# User_Control-Sliders.net
KiCad netlist of a schematic drawn in Altium Designer
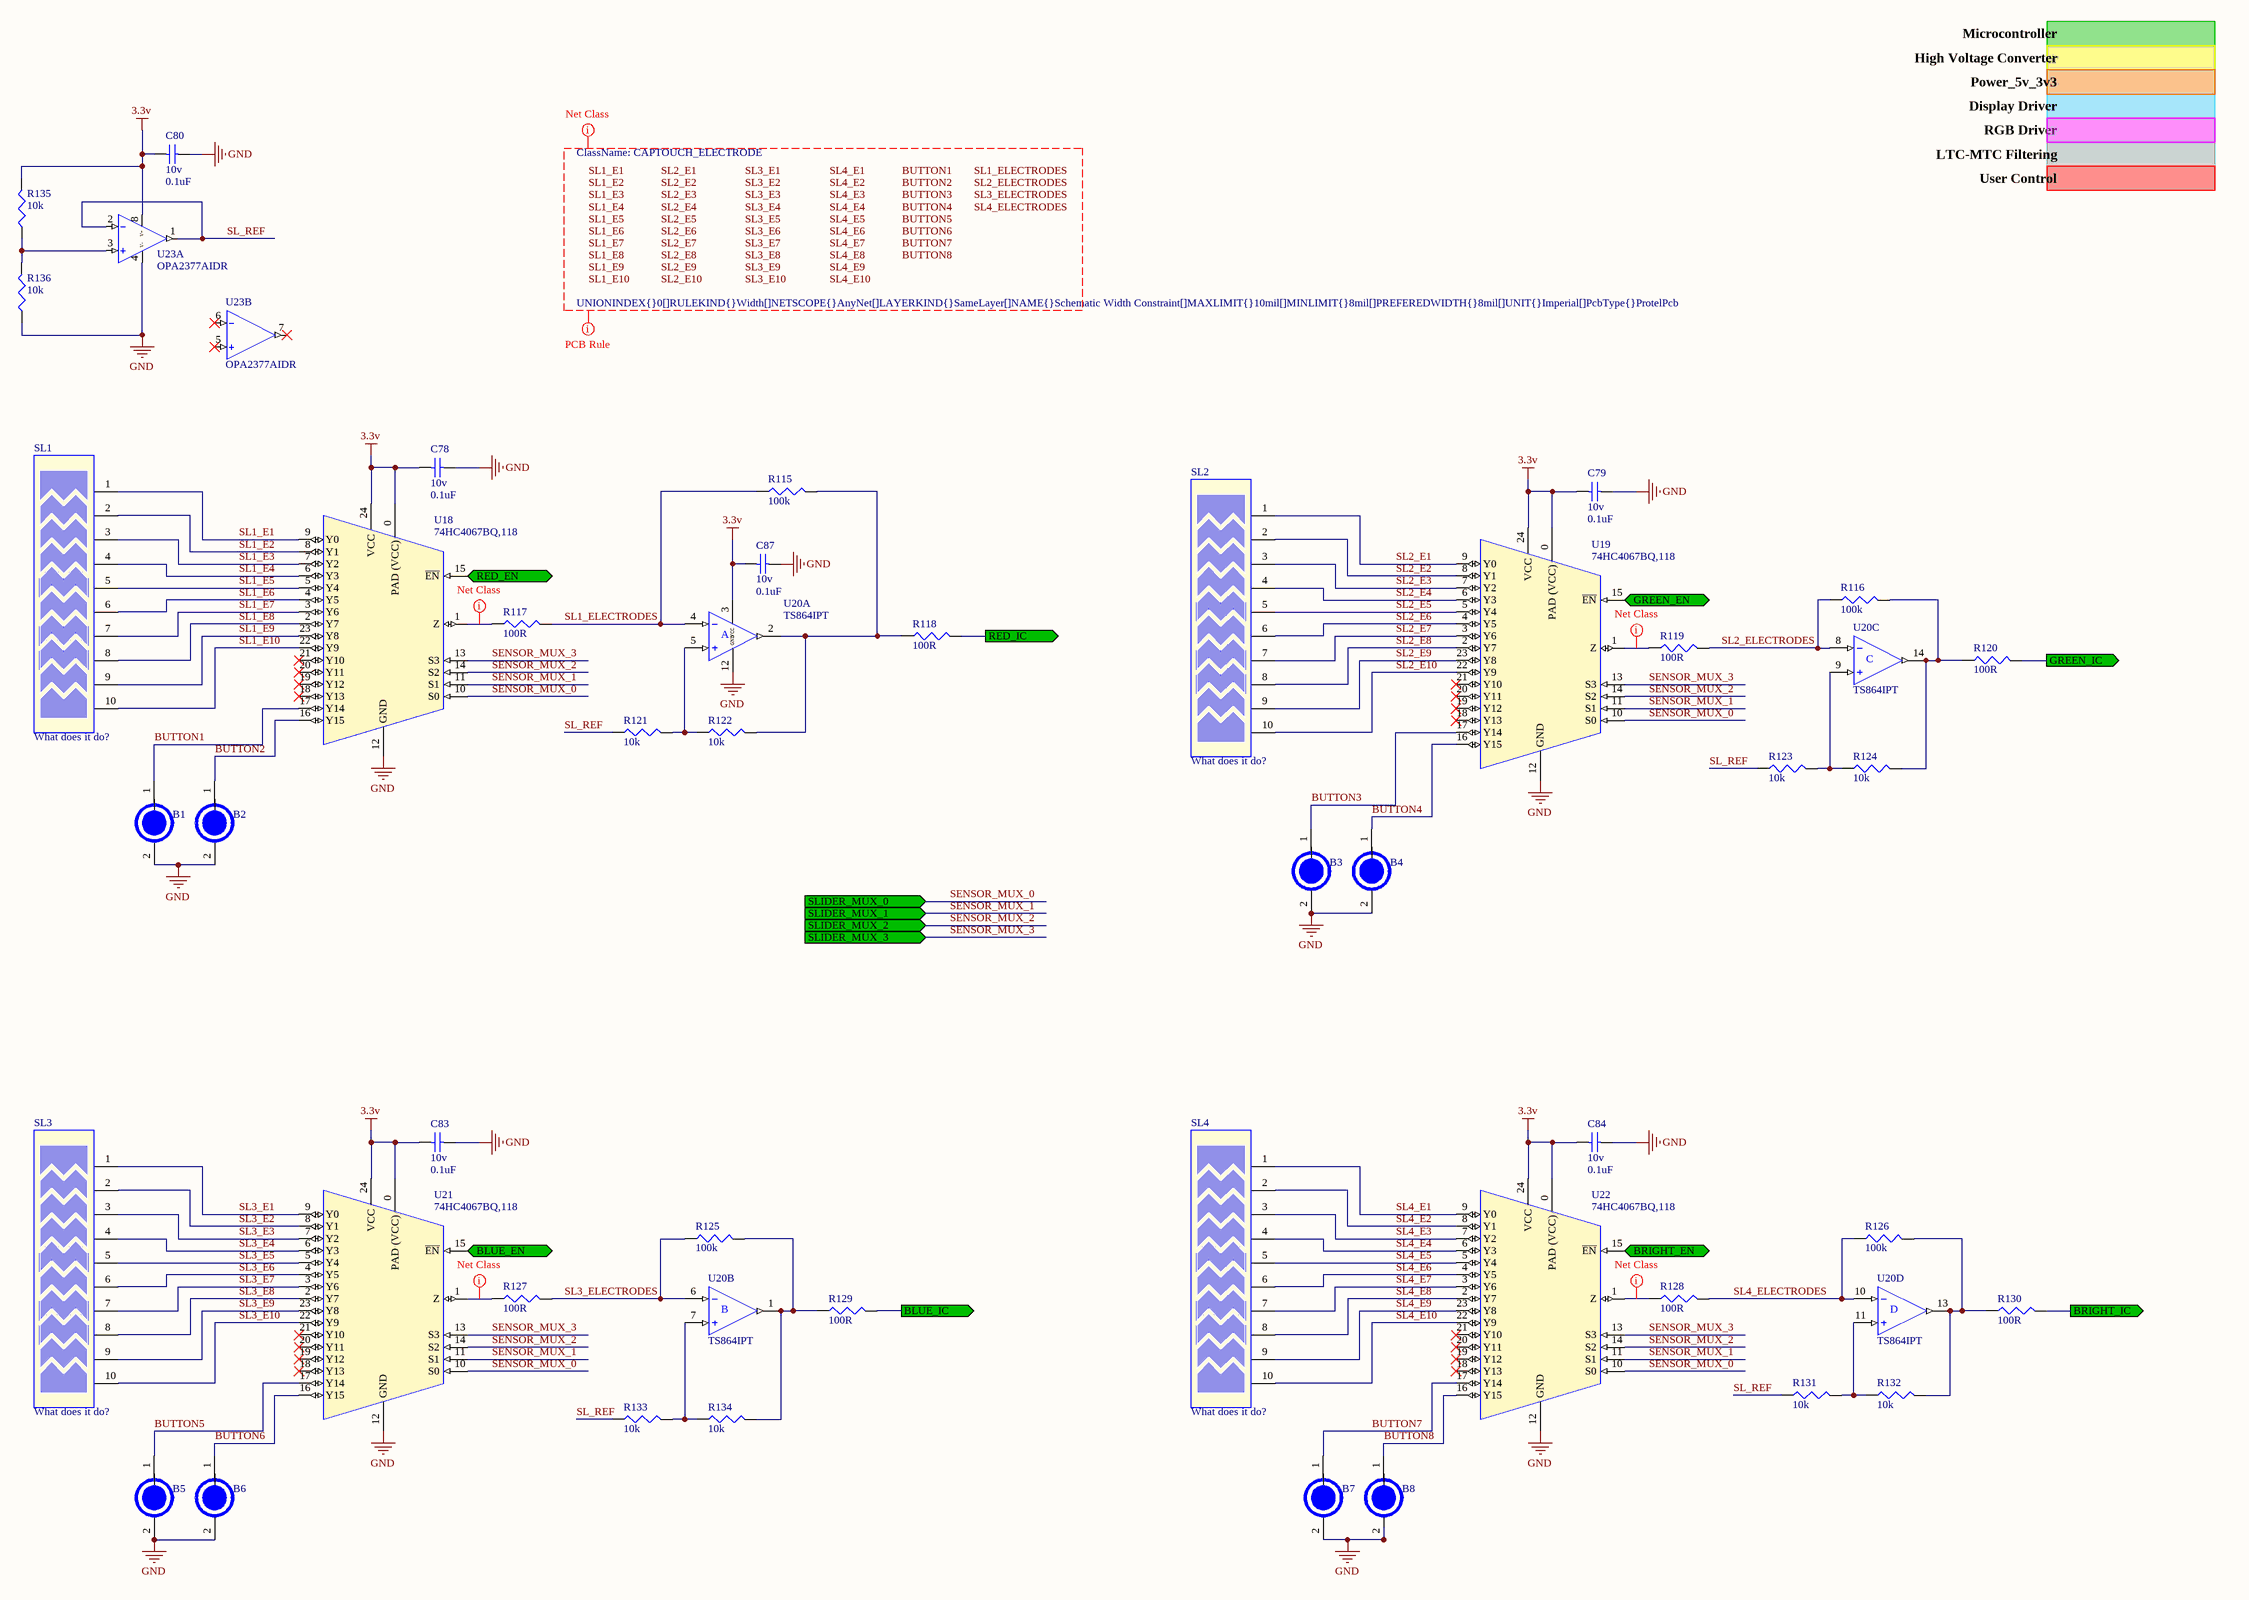
[diagram p0: User Control-Sliders.SchDoc]

(export (version "E")
  (design (tool "Eeschema 10.0.6"))
  (components
    (comp (ref "B1")
      (value "Cap Touch Button")
      (footprint "Cap Touch Button 10mm")
      (libsource (lib "Altium Library") (part "Cap Touch Button 10mm"))
    )
    (comp (ref "B2")
      (value "Cap Touch Button")
      (footprint "Cap Touch Button 10mm")
      (libsource (lib "Altium Library") (part "Cap Touch Button 10mm"))
    )
    (comp (ref "B3")
      (value "Cap Touch Button")
      (footprint "Cap Touch Button 10mm")
      (libsource (lib "Altium Library") (part "Cap Touch Button 10mm"))
    )
    (comp (ref "B4")
      (value "Cap Touch Button")
      (footprint "Cap Touch Button 10mm")
      (libsource (lib "Altium Library") (part "Cap Touch Button 10mm"))
    )
    (comp (ref "B5")
      (value "Cap Touch Button")
      (footprint "Cap Touch Button 10mm")
      (libsource (lib "Altium Library") (part "Cap Touch Button 10mm"))
    )
    (comp (ref "B6")
      (value "Cap Touch Button")
      (footprint "Cap Touch Button 10mm")
      (libsource (lib "Altium Library") (part "Cap Touch Button 10mm"))
    )
    (comp (ref "B7")
      (value "Cap Touch Button")
      (footprint "Cap Touch Button 10mm")
      (libsource (lib "Altium Library") (part "Cap Touch Button 10mm"))
    )
    (comp (ref "B8")
      (value "Cap Touch Button")
      (footprint "Cap Touch Button 10mm")
      (libsource (lib "Altium Library") (part "Cap Touch Button 10mm"))
    )
    (comp (ref "C78")
      (value "0.1uF")
      (footprint "CAP0402R")
      (fields (field (name "TOLERANCE") "20%") (field (name "MFG") "Vishay") (field (name "VOLTAGE") "10v"))
      (libsource (lib "Altium Library") (part "0.1uF 10v (0402)"))
    )
    (comp (ref "C79")
      (value "0.1uF")
      (footprint "CAP0402R")
      (fields (field (name "TOLERANCE") "20%") (field (name "MFG") "Vishay") (field (name "VOLTAGE") "10v"))
      (libsource (lib "Altium Library") (part "0.1uF 10v (0402)"))
    )
    (comp (ref "C80")
      (value "0.1uF")
      (footprint "CAP0402R")
      (fields (field (name "TOLERANCE") "20%") (field (name "MFG") "Vishay") (field (name "VOLTAGE") "10v"))
      (libsource (lib "Altium Library") (part "0.1uF 10v (0402)"))
    )
    (comp (ref "C83")
      (value "0.1uF")
      (footprint "CAP0402R")
      (fields (field (name "TOLERANCE") "20%") (field (name "MFG") "Vishay") (field (name "VOLTAGE") "10v"))
      (libsource (lib "Altium Library") (part "0.1uF 10v (0402)"))
    )
    (comp (ref "C84")
      (value "0.1uF")
      (footprint "CAP0402R")
      (fields (field (name "TOLERANCE") "20%") (field (name "MFG") "Vishay") (field (name "VOLTAGE") "10v"))
      (libsource (lib "Altium Library") (part "0.1uF 10v (0402)"))
    )
    (comp (ref "C87")
      (value "0.1uF")
      (footprint "CAP0402R")
      (fields (field (name "TOLERANCE") "20%") (field (name "MFG") "Vishay") (field (name "VOLTAGE") "10v"))
      (libsource (lib "Altium Library") (part "0.1uF 10v (0402)"))
    )
    (comp (ref "R115")
      (value "100k")
      (footprint "RES0402R")
      (fields (field (name "TOLERANCE") "1%") (field (name "POWER") "63mW") (field (name "MFG") "Vishay"))
      (libsource (lib "Altium Library") (part "100k (0402)"))
    )
    (comp (ref "R116")
      (value "100k")
      (footprint "RES0402R")
      (fields (field (name "TOLERANCE") "1%") (field (name "POWER") "63mW") (field (name "MFG") "Vishay"))
      (libsource (lib "Altium Library") (part "100k (0402)"))
    )
    (comp (ref "R117")
      (value "100R")
      (footprint "RES0402R")
      (fields (field (name "TOLERANCE") "1%") (field (name "POWER") "63mW") (field (name "MFG") "Vishay"))
      (libsource (lib "Altium Library") (part "100R (0402)"))
    )
    (comp (ref "R118")
      (value "100R")
      (footprint "RES0402R")
      (fields (field (name "TOLERANCE") "1%") (field (name "POWER") "63mW") (field (name "MFG") "Vishay"))
      (libsource (lib "Altium Library") (part "100R (0402)"))
    )
    (comp (ref "R119")
      (value "100R")
      (footprint "RES0402R")
      (fields (field (name "TOLERANCE") "1%") (field (name "POWER") "63mW") (field (name "MFG") "Vishay"))
      (libsource (lib "Altium Library") (part "100R (0402)"))
    )
    (comp (ref "R120")
      (value "100R")
      (footprint "RES0402R")
      (fields (field (name "TOLERANCE") "1%") (field (name "POWER") "63mW") (field (name "MFG") "Vishay"))
      (libsource (lib "Altium Library") (part "100R (0402)"))
    )
    (comp (ref "R121")
      (value "10k")
      (footprint "RES0402R")
      (fields (field (name "TOLERANCE") "1%") (field (name "POWER") "63mW") (field (name "MFG") "Vishay"))
      (libsource (lib "Altium Library") (part "10k (0402)"))
    )
    (comp (ref "R122")
      (value "10k")
      (footprint "RES0402R")
      (fields (field (name "TOLERANCE") "1%") (field (name "POWER") "63mW") (field (name "MFG") "Vishay"))
      (libsource (lib "Altium Library") (part "10k (0402)"))
    )
    (comp (ref "R123")
      (value "10k")
      (footprint "RES0402R")
      (fields (field (name "TOLERANCE") "1%") (field (name "POWER") "63mW") (field (name "MFG") "Vishay"))
      (libsource (lib "Altium Library") (part "10k (0402)"))
    )
    (comp (ref "R124")
      (value "10k")
      (footprint "RES0402R")
      (fields (field (name "TOLERANCE") "1%") (field (name "POWER") "63mW") (field (name "MFG") "Vishay"))
      (libsource (lib "Altium Library") (part "10k (0402)"))
    )
    (comp (ref "R125")
      (value "100k")
      (footprint "RES0402R")
      (fields (field (name "TOLERANCE") "1%") (field (name "POWER") "63mW") (field (name "MFG") "Vishay"))
      (libsource (lib "Altium Library") (part "100k (0402)"))
    )
    (comp (ref "R126")
      (value "100k")
      (footprint "RES0402R")
      (fields (field (name "TOLERANCE") "1%") (field (name "POWER") "63mW") (field (name "MFG") "Vishay"))
      (libsource (lib "Altium Library") (part "100k (0402)"))
    )
    (comp (ref "R127")
      (value "100R")
      (footprint "RES0402R")
      (fields (field (name "TOLERANCE") "1%") (field (name "POWER") "63mW") (field (name "MFG") "Vishay"))
      (libsource (lib "Altium Library") (part "100R (0402)"))
    )
    (comp (ref "R128")
      (value "100R")
      (footprint "RES0402R")
      (fields (field (name "TOLERANCE") "1%") (field (name "POWER") "63mW") (field (name "MFG") "Vishay"))
      (libsource (lib "Altium Library") (part "100R (0402)"))
    )
    (comp (ref "R129")
      (value "100R")
      (footprint "RES0402R")
      (fields (field (name "TOLERANCE") "1%") (field (name "POWER") "63mW") (field (name "MFG") "Vishay"))
      (libsource (lib "Altium Library") (part "100R (0402)"))
    )
    (comp (ref "R130")
      (value "100R")
      (footprint "RES0402R")
      (fields (field (name "TOLERANCE") "1%") (field (name "POWER") "63mW") (field (name "MFG") "Vishay"))
      (libsource (lib "Altium Library") (part "100R (0402)"))
    )
    (comp (ref "R131")
      (value "10k")
      (footprint "RES0402R")
      (fields (field (name "TOLERANCE") "1%") (field (name "POWER") "63mW") (field (name "MFG") "Vishay"))
      (libsource (lib "Altium Library") (part "10k (0402)"))
    )
    (comp (ref "R132")
      (value "10k")
      (footprint "RES0402R")
      (fields (field (name "TOLERANCE") "1%") (field (name "POWER") "63mW") (field (name "MFG") "Vishay"))
      (libsource (lib "Altium Library") (part "10k (0402)"))
    )
    (comp (ref "R133")
      (value "10k")
      (footprint "RES0402R")
      (fields (field (name "TOLERANCE") "1%") (field (name "POWER") "63mW") (field (name "MFG") "Vishay"))
      (libsource (lib "Altium Library") (part "10k (0402)"))
    )
    (comp (ref "R134")
      (value "10k")
      (footprint "RES0402R")
      (fields (field (name "TOLERANCE") "1%") (field (name "POWER") "63mW") (field (name "MFG") "Vishay"))
      (libsource (lib "Altium Library") (part "10k (0402)"))
    )
    (comp (ref "R135")
      (value "10k")
      (footprint "RES0402R")
      (fields (field (name "TOLERANCE") "1%") (field (name "POWER") "63mW") (field (name "MFG") "Vishay"))
      (libsource (lib "Altium Library") (part "10k (0402)"))
    )
    (comp (ref "R136")
      (value "10k")
      (footprint "RES0402R")
      (fields (field (name "TOLERANCE") "1%") (field (name "POWER") "63mW") (field (name "MFG") "Vishay"))
      (libsource (lib "Altium Library") (part "10k (0402)"))
    )
    (comp (ref "SL1")
      (value "What does it do?")
      (footprint "Cap Slider 15x55mm")
      (libsource (lib "Altium Library") (part "Capacitive Slider 10-position 15x55mm"))
    )
    (comp (ref "SL2")
      (value "What does it do?")
      (footprint "Cap Slider 15x55mm")
      (libsource (lib "Altium Library") (part "Capacitive Slider 10-position 15x55mm"))
    )
    (comp (ref "SL3")
      (value "What does it do?")
      (footprint "Cap Slider 15x55mm")
      (libsource (lib "Altium Library") (part "Capacitive Slider 10-position 15x55mm"))
    )
    (comp (ref "SL4")
      (value "What does it do?")
      (footprint "Cap Slider 15x55mm")
      (libsource (lib "Altium Library") (part "Capacitive Slider 10-position 15x55mm"))
    )
    (comp (ref "U18")
      (value "74HC4067BQ,118")
      (footprint "SOT815-1")
      (description "Analog MUX/DEMUX, 16-Channel, 42ns")
      (fields (field (name "MFG") "NXP"))
      (libsource (lib "Altium Library") (part "74HC4067BQ,118"))
    )
    (comp (ref "U19")
      (value "74HC4067BQ,118")
      (footprint "SOT815-1")
      (description "Analog MUX/DEMUX, 16-Channel, 42ns")
      (fields (field (name "MFG") "NXP"))
      (libsource (lib "Altium Library") (part "74HC4067BQ,118"))
    )
    (comp (ref "U20")
      (value "TS864IPT")
      (footprint "TSSOP14")
      (description "Compartor, Quad, 2.7-10v, 20ns")
      (fields (field (name "MFG") "ST"))
      (libsource (lib "Altium Library") (part "TS864IPT"))
    )
    (comp (ref "U21")
      (value "74HC4067BQ,118")
      (footprint "SOT815-1")
      (description "Analog MUX/DEMUX, 16-Channel, 42ns")
      (fields (field (name "MFG") "NXP"))
      (libsource (lib "Altium Library") (part "74HC4067BQ,118"))
    )
    (comp (ref "U22")
      (value "74HC4067BQ,118")
      (footprint "SOT815-1")
      (description "Analog MUX/DEMUX, 16-Channel, 42ns")
      (fields (field (name "MFG") "NXP"))
      (libsource (lib "Altium Library") (part "74HC4067BQ,118"))
    )
    (comp (ref "U23")
      (value "OPA2377AIDR")
      (footprint "SOIC-8")
      (description "OpAmp - 2 Channel")
      (fields (field (name "MFG") "TI"))
      (libsource (lib "Altium Library") (part "OPA2377AIDR"))
    )
  )
  (nets
    (net (code "1") (name "/BLUE_EN") (class "Default")
      (node (ref "U21") (pin "15") (pinfunction "~{EN}_15") (pintype "input"))
    )
    (net (code "2") (name "/BLUE_IC") (class "Default")
      (node (ref "R129") (pin "2") (pinfunction "2_2") (pintype "passive"))
    )
    (net (code "3") (name "/BRIGHT_EN") (class "Default")
      (node (ref "U22") (pin "15") (pinfunction "~{EN}_15") (pintype "input"))
    )
    (net (code "4") (name "/BRIGHT_IC") (class "Default")
      (node (ref "R130") (pin "2") (pinfunction "2_2") (pintype "passive"))
    )
    (net (code "5") (name "/BUTTON1") (class "Default")
      (node (ref "B1") (pin "1") (pinfunction "+_1") (pintype "passive"))
      (node (ref "U18") (pin "17") (pinfunction "Y14_17") (pintype "bidirectional"))
    )
    (net (code "6") (name "/BUTTON2") (class "Default")
      (node (ref "B2") (pin "1") (pinfunction "+_1") (pintype "passive"))
      (node (ref "U18") (pin "16") (pinfunction "Y15_16") (pintype "bidirectional"))
    )
    (net (code "7") (name "/BUTTON3") (class "Default")
      (node (ref "B3") (pin "1") (pinfunction "+_1") (pintype "passive"))
      (node (ref "U19") (pin "17") (pinfunction "Y14_17") (pintype "bidirectional"))
    )
    (net (code "8") (name "/BUTTON4") (class "Default")
      (node (ref "B4") (pin "1") (pinfunction "+_1") (pintype "passive"))
      (node (ref "U19") (pin "16") (pinfunction "Y15_16") (pintype "bidirectional"))
    )
    (net (code "9") (name "/BUTTON5") (class "Default")
      (node (ref "B5") (pin "1") (pinfunction "+_1") (pintype "passive"))
      (node (ref "U21") (pin "17") (pinfunction "Y14_17") (pintype "bidirectional"))
    )
    (net (code "10") (name "/BUTTON6") (class "Default")
      (node (ref "B6") (pin "1") (pinfunction "+_1") (pintype "passive"))
      (node (ref "U21") (pin "16") (pinfunction "Y15_16") (pintype "bidirectional"))
    )
    (net (code "11") (name "/BUTTON7") (class "Default")
      (node (ref "B7") (pin "1") (pinfunction "+_1") (pintype "passive"))
      (node (ref "U22") (pin "17") (pinfunction "Y14_17") (pintype "bidirectional"))
    )
    (net (code "12") (name "/BUTTON8") (class "Default")
      (node (ref "B8") (pin "1") (pinfunction "+_1") (pintype "passive"))
      (node (ref "U22") (pin "16") (pinfunction "Y15_16") (pintype "bidirectional"))
    )
    (net (code "13") (name "/GREEN_EN") (class "Default")
      (node (ref "U19") (pin "15") (pinfunction "~{EN}_15") (pintype "input"))
    )
    (net (code "14") (name "/GREEN_IC") (class "Default")
      (node (ref "R120") (pin "2") (pinfunction "2_2") (pintype "passive"))
    )
    (net (code "15") (name "/RED_EN") (class "Default")
      (node (ref "U18") (pin "15") (pinfunction "~{EN}_15") (pintype "input"))
    )
    (net (code "16") (name "/RED_IC") (class "Default")
      (node (ref "R118") (pin "2") (pinfunction "2_2") (pintype "passive"))
    )
    (net (code "17") (name "/SENSOR_MUX_0") (class "Default")
      (node (ref "U18") (pin "10") (pinfunction "S0_10") (pintype "input"))
      (node (ref "U19") (pin "10") (pinfunction "S0_10") (pintype "input"))
      (node (ref "U21") (pin "10") (pinfunction "S0_10") (pintype "input"))
      (node (ref "U22") (pin "10") (pinfunction "S0_10") (pintype "input"))
    )
    (net (code "18") (name "/SENSOR_MUX_1") (class "Default")
      (node (ref "U18") (pin "11") (pinfunction "S1_11") (pintype "input"))
      (node (ref "U19") (pin "11") (pinfunction "S1_11") (pintype "input"))
      (node (ref "U21") (pin "11") (pinfunction "S1_11") (pintype "input"))
      (node (ref "U22") (pin "11") (pinfunction "S1_11") (pintype "input"))
    )
    (net (code "19") (name "/SENSOR_MUX_2") (class "Default")
      (node (ref "U18") (pin "14") (pinfunction "S2_14") (pintype "input"))
      (node (ref "U19") (pin "14") (pinfunction "S2_14") (pintype "input"))
      (node (ref "U21") (pin "14") (pinfunction "S2_14") (pintype "input"))
      (node (ref "U22") (pin "14") (pinfunction "S2_14") (pintype "input"))
    )
    (net (code "20") (name "/SENSOR_MUX_3") (class "Default")
      (node (ref "U18") (pin "13") (pinfunction "S3_13") (pintype "input"))
      (node (ref "U19") (pin "13") (pinfunction "S3_13") (pintype "input"))
      (node (ref "U21") (pin "13") (pinfunction "S3_13") (pintype "input"))
      (node (ref "U22") (pin "13") (pinfunction "S3_13") (pintype "input"))
    )
    (net (code "21") (name "/SL1_E1") (class "Default")
      (node (ref "SL1") (pin "1") (pinfunction "1_1") (pintype "passive"))
      (node (ref "U18") (pin "9") (pinfunction "Y0_9") (pintype "bidirectional"))
    )
    (net (code "22") (name "/SL1_E2") (class "Default")
      (node (ref "SL1") (pin "2") (pinfunction "2_2") (pintype "passive"))
      (node (ref "U18") (pin "8") (pinfunction "Y1_8") (pintype "bidirectional"))
    )
    (net (code "23") (name "/SL1_E3") (class "Default")
      (node (ref "SL1") (pin "3") (pinfunction "3_3") (pintype "passive"))
      (node (ref "U18") (pin "7") (pinfunction "Y2_7") (pintype "bidirectional"))
    )
    (net (code "24") (name "/SL1_E4") (class "Default")
      (node (ref "SL1") (pin "4") (pinfunction "4_4") (pintype "passive"))
      (node (ref "U18") (pin "6") (pinfunction "Y3_6") (pintype "bidirectional"))
    )
    (net (code "25") (name "/SL1_E5") (class "Default")
      (node (ref "SL1") (pin "5") (pinfunction "5_5") (pintype "passive"))
      (node (ref "U18") (pin "5") (pinfunction "Y4_5") (pintype "bidirectional"))
    )
    (net (code "26") (name "/SL1_E6") (class "Default")
      (node (ref "SL1") (pin "6") (pinfunction "6_6") (pintype "passive"))
      (node (ref "U18") (pin "4") (pinfunction "Y5_4") (pintype "bidirectional"))
    )
    (net (code "27") (name "/SL1_E7") (class "Default")
      (node (ref "SL1") (pin "7") (pinfunction "7_7") (pintype "passive"))
      (node (ref "U18") (pin "3") (pinfunction "Y6_3") (pintype "bidirectional"))
    )
    (net (code "28") (name "/SL1_E8") (class "Default")
      (node (ref "SL1") (pin "8") (pinfunction "8_8") (pintype "passive"))
      (node (ref "U18") (pin "2") (pinfunction "Y7_2") (pintype "bidirectional"))
    )
    (net (code "29") (name "/SL1_E9") (class "Default")
      (node (ref "SL1") (pin "9") (pinfunction "9_9") (pintype "passive"))
      (node (ref "U18") (pin "23") (pinfunction "Y8_23") (pintype "bidirectional"))
    )
    (net (code "30") (name "/SL1_E10") (class "Default")
      (node (ref "SL1") (pin "10") (pinfunction "10_10") (pintype "passive"))
      (node (ref "U18") (pin "22") (pinfunction "Y9_22") (pintype "bidirectional"))
    )
    (net (code "31") (name "/SL1_ELECTRODES") (class "Default")
      (node (ref "R115") (pin "1") (pinfunction "1_1") (pintype "passive"))
      (node (ref "R117") (pin "2") (pinfunction "2_2") (pintype "passive"))
      (node (ref "U20") (pin "4") (pinfunction "1IN-_4") (pintype "input"))
    )
    (net (code "32") (name "/SL2_E1") (class "Default")
      (node (ref "SL2") (pin "1") (pinfunction "1_1") (pintype "passive"))
      (node (ref "U19") (pin "9") (pinfunction "Y0_9") (pintype "bidirectional"))
    )
    (net (code "33") (name "/SL2_E2") (class "Default")
      (node (ref "SL2") (pin "2") (pinfunction "2_2") (pintype "passive"))
      (node (ref "U19") (pin "8") (pinfunction "Y1_8") (pintype "bidirectional"))
    )
    (net (code "34") (name "/SL2_E3") (class "Default")
      (node (ref "SL2") (pin "3") (pinfunction "3_3") (pintype "passive"))
      (node (ref "U19") (pin "7") (pinfunction "Y2_7") (pintype "bidirectional"))
    )
    (net (code "35") (name "/SL2_E4") (class "Default")
      (node (ref "SL2") (pin "4") (pinfunction "4_4") (pintype "passive"))
      (node (ref "U19") (pin "6") (pinfunction "Y3_6") (pintype "bidirectional"))
    )
    (net (code "36") (name "/SL2_E5") (class "Default")
      (node (ref "SL2") (pin "5") (pinfunction "5_5") (pintype "passive"))
      (node (ref "U19") (pin "5") (pinfunction "Y4_5") (pintype "bidirectional"))
    )
    (net (code "37") (name "/SL2_E6") (class "Default")
      (node (ref "SL2") (pin "6") (pinfunction "6_6") (pintype "passive"))
      (node (ref "U19") (pin "4") (pinfunction "Y5_4") (pintype "bidirectional"))
    )
    (net (code "38") (name "/SL2_E7") (class "Default")
      (node (ref "SL2") (pin "7") (pinfunction "7_7") (pintype "passive"))
      (node (ref "U19") (pin "3") (pinfunction "Y6_3") (pintype "bidirectional"))
    )
    (net (code "39") (name "/SL2_E8") (class "Default")
      (node (ref "SL2") (pin "8") (pinfunction "8_8") (pintype "passive"))
      (node (ref "U19") (pin "2") (pinfunction "Y7_2") (pintype "bidirectional"))
    )
    (net (code "40") (name "/SL2_E9") (class "Default")
      (node (ref "SL2") (pin "9") (pinfunction "9_9") (pintype "passive"))
      (node (ref "U19") (pin "23") (pinfunction "Y8_23") (pintype "bidirectional"))
    )
    (net (code "41") (name "/SL2_E10") (class "Default")
      (node (ref "SL2") (pin "10") (pinfunction "10_10") (pintype "passive"))
      (node (ref "U19") (pin "22") (pinfunction "Y9_22") (pintype "bidirectional"))
    )
    (net (code "42") (name "/SL2_ELECTRODES") (class "Default")
      (node (ref "R116") (pin "1") (pinfunction "1_1") (pintype "passive"))
      (node (ref "R119") (pin "2") (pinfunction "2_2") (pintype "passive"))
      (node (ref "U20") (pin "8") (pinfunction "3IN-_8") (pintype "input"))
    )
    (net (code "43") (name "/SL3_E1") (class "Default")
      (node (ref "SL3") (pin "1") (pinfunction "1_1") (pintype "passive"))
      (node (ref "U21") (pin "9") (pinfunction "Y0_9") (pintype "bidirectional"))
    )
    (net (code "44") (name "/SL3_E2") (class "Default")
      (node (ref "SL3") (pin "2") (pinfunction "2_2") (pintype "passive"))
      (node (ref "U21") (pin "8") (pinfunction "Y1_8") (pintype "bidirectional"))
    )
    (net (code "45") (name "/SL3_E3") (class "Default")
      (node (ref "SL3") (pin "3") (pinfunction "3_3") (pintype "passive"))
      (node (ref "U21") (pin "7") (pinfunction "Y2_7") (pintype "bidirectional"))
    )
    (net (code "46") (name "/SL3_E4") (class "Default")
      (node (ref "SL3") (pin "4") (pinfunction "4_4") (pintype "passive"))
      (node (ref "U21") (pin "6") (pinfunction "Y3_6") (pintype "bidirectional"))
    )
    (net (code "47") (name "/SL3_E5") (class "Default")
      (node (ref "SL3") (pin "5") (pinfunction "5_5") (pintype "passive"))
      (node (ref "U21") (pin "5") (pinfunction "Y4_5") (pintype "bidirectional"))
    )
    (net (code "48") (name "/SL3_E6") (class "Default")
      (node (ref "SL3") (pin "6") (pinfunction "6_6") (pintype "passive"))
      (node (ref "U21") (pin "4") (pinfunction "Y5_4") (pintype "bidirectional"))
    )
    (net (code "49") (name "/SL3_E7") (class "Default")
      (node (ref "SL3") (pin "7") (pinfunction "7_7") (pintype "passive"))
      (node (ref "U21") (pin "3") (pinfunction "Y6_3") (pintype "bidirectional"))
    )
    (net (code "50") (name "/SL3_E8") (class "Default")
      (node (ref "SL3") (pin "8") (pinfunction "8_8") (pintype "passive"))
      (node (ref "U21") (pin "2") (pinfunction "Y7_2") (pintype "bidirectional"))
    )
    (net (code "51") (name "/SL3_E9") (class "Default")
      (node (ref "SL3") (pin "9") (pinfunction "9_9") (pintype "passive"))
      (node (ref "U21") (pin "23") (pinfunction "Y8_23") (pintype "bidirectional"))
    )
    (net (code "52") (name "/SL3_E10") (class "Default")
      (node (ref "SL3") (pin "10") (pinfunction "10_10") (pintype "passive"))
      (node (ref "U21") (pin "22") (pinfunction "Y9_22") (pintype "bidirectional"))
    )
    (net (code "53") (name "/SL3_ELECTRODES") (class "Default")
      (node (ref "R125") (pin "1") (pinfunction "1_1") (pintype "passive"))
      (node (ref "R127") (pin "2") (pinfunction "2_2") (pintype "passive"))
      (node (ref "U20") (pin "6") (pinfunction "2IN-_6") (pintype "input"))
    )
    (net (code "54") (name "/SL4_E1") (class "Default")
      (node (ref "SL4") (pin "1") (pinfunction "1_1") (pintype "passive"))
      (node (ref "U22") (pin "9") (pinfunction "Y0_9") (pintype "bidirectional"))
    )
    (net (code "55") (name "/SL4_E2") (class "Default")
      (node (ref "SL4") (pin "2") (pinfunction "2_2") (pintype "passive"))
      (node (ref "U22") (pin "8") (pinfunction "Y1_8") (pintype "bidirectional"))
    )
    (net (code "56") (name "/SL4_E3") (class "Default")
      (node (ref "SL4") (pin "3") (pinfunction "3_3") (pintype "passive"))
      (node (ref "U22") (pin "7") (pinfunction "Y2_7") (pintype "bidirectional"))
    )
    (net (code "57") (name "/SL4_E4") (class "Default")
      (node (ref "SL4") (pin "4") (pinfunction "4_4") (pintype "passive"))
      (node (ref "U22") (pin "6") (pinfunction "Y3_6") (pintype "bidirectional"))
    )
    (net (code "58") (name "/SL4_E5") (class "Default")
      (node (ref "SL4") (pin "5") (pinfunction "5_5") (pintype "passive"))
      (node (ref "U22") (pin "5") (pinfunction "Y4_5") (pintype "bidirectional"))
    )
    (net (code "59") (name "/SL4_E6") (class "Default")
      (node (ref "SL4") (pin "6") (pinfunction "6_6") (pintype "passive"))
      (node (ref "U22") (pin "4") (pinfunction "Y5_4") (pintype "bidirectional"))
    )
    (net (code "60") (name "/SL4_E7") (class "Default")
      (node (ref "SL4") (pin "7") (pinfunction "7_7") (pintype "passive"))
      (node (ref "U22") (pin "3") (pinfunction "Y6_3") (pintype "bidirectional"))
    )
    (net (code "61") (name "/SL4_E8") (class "Default")
      (node (ref "SL4") (pin "8") (pinfunction "8_8") (pintype "passive"))
      (node (ref "U22") (pin "2") (pinfunction "Y7_2") (pintype "bidirectional"))
    )
    (net (code "62") (name "/SL4_E9") (class "Default")
      (node (ref "SL4") (pin "9") (pinfunction "9_9") (pintype "passive"))
      (node (ref "U22") (pin "23") (pinfunction "Y8_23") (pintype "bidirectional"))
    )
    (net (code "63") (name "/SL4_E10") (class "Default")
      (node (ref "SL4") (pin "10") (pinfunction "10_10") (pintype "passive"))
      (node (ref "U22") (pin "22") (pinfunction "Y9_22") (pintype "bidirectional"))
    )
    (net (code "64") (name "/SL4_ELECTRODES") (class "Default")
      (node (ref "R126") (pin "1") (pinfunction "1_1") (pintype "passive"))
      (node (ref "R128") (pin "2") (pinfunction "2_2") (pintype "passive"))
      (node (ref "U20") (pin "10") (pinfunction "4IN-_10") (pintype "input"))
    )
    (net (code "65") (name "/SL_REF") (class "Default")
      (node (ref "R121") (pin "1") (pinfunction "1_1") (pintype "passive"))
      (node (ref "R123") (pin "1") (pinfunction "1_1") (pintype "passive"))
      (node (ref "R131") (pin "1") (pinfunction "1_1") (pintype "passive"))
      (node (ref "R133") (pin "1") (pinfunction "1_1") (pintype "passive"))
      (node (ref "U23") (pin "1") (pinfunction "OUT_A_1") (pintype "output"))
      (node (ref "U23") (pin "2") (pinfunction "-IN_A_2") (pintype "input"))
    )
    (net (code "66") (name "3.3v") (class "Default")
      (node (ref "C78") (pin "1") (pinfunction "1_1") (pintype "passive"))
      (node (ref "C79") (pin "1") (pinfunction "1_1") (pintype "passive"))
      (node (ref "C80") (pin "2") (pinfunction "2_2") (pintype "passive"))
      (node (ref "C83") (pin "1") (pinfunction "1_1") (pintype "passive"))
      (node (ref "C84") (pin "1") (pinfunction "1_1") (pintype "passive"))
      (node (ref "C87") (pin "1") (pinfunction "1_1") (pintype "passive"))
      (node (ref "R135") (pin "2") (pinfunction "2_2") (pintype "passive"))
      (node (ref "U18") (pin "0") (pinfunction "PAD_(VCC)_0") (pintype "power_in"))
      (node (ref "U18") (pin "24") (pinfunction "VCC_24") (pintype "power_in"))
      (node (ref "U19") (pin "0") (pinfunction "PAD_(VCC)_0") (pintype "power_in"))
      (node (ref "U19") (pin "24") (pinfunction "VCC_24") (pintype "power_in"))
      (node (ref "U20") (pin "3") (pinfunction "VCC_3") (pintype "power_in"))
      (node (ref "U21") (pin "0") (pinfunction "PAD_(VCC)_0") (pintype "power_in"))
      (node (ref "U21") (pin "24") (pinfunction "VCC_24") (pintype "power_in"))
      (node (ref "U22") (pin "0") (pinfunction "PAD_(VCC)_0") (pintype "power_in"))
      (node (ref "U22") (pin "24") (pinfunction "VCC_24") (pintype "power_in"))
      (node (ref "U23") (pin "8") (pinfunction "V+_8") (pintype "power_in"))
    )
    (net (code "67") (name "GND") (class "Default")
      (node (ref "B1") (pin "2") (pinfunction "-_2") (pintype "passive"))
      (node (ref "B2") (pin "2") (pinfunction "-_2") (pintype "passive"))
      (node (ref "B3") (pin "2") (pinfunction "-_2") (pintype "passive"))
      (node (ref "B4") (pin "2") (pinfunction "-_2") (pintype "passive"))
      (node (ref "B5") (pin "2") (pinfunction "-_2") (pintype "passive"))
      (node (ref "B6") (pin "2") (pinfunction "-_2") (pintype "passive"))
      (node (ref "B7") (pin "2") (pinfunction "-_2") (pintype "passive"))
      (node (ref "B8") (pin "2") (pinfunction "-_2") (pintype "passive"))
      (node (ref "C78") (pin "2") (pinfunction "2_2") (pintype "passive"))
      (node (ref "C79") (pin "2") (pinfunction "2_2") (pintype "passive"))
      (node (ref "C80") (pin "1") (pinfunction "1_1") (pintype "passive"))
      (node (ref "C83") (pin "2") (pinfunction "2_2") (pintype "passive"))
      (node (ref "C84") (pin "2") (pinfunction "2_2") (pintype "passive"))
      (node (ref "C87") (pin "2") (pinfunction "2_2") (pintype "passive"))
      (node (ref "R136") (pin "1") (pinfunction "1_1") (pintype "passive"))
      (node (ref "U18") (pin "12") (pinfunction "GND_12") (pintype "power_in"))
      (node (ref "U19") (pin "12") (pinfunction "GND_12") (pintype "power_in"))
      (node (ref "U20") (pin "12") (pinfunction "GND_12") (pintype "power_in"))
      (node (ref "U21") (pin "12") (pinfunction "GND_12") (pintype "power_in"))
      (node (ref "U22") (pin "12") (pinfunction "GND_12") (pintype "power_in"))
      (node (ref "U23") (pin "4") (pinfunction "V-_4") (pintype "power_in"))
    )
    (net (code "68") (name "Net-(U18-Z)") (class "Default")
      (node (ref "R117") (pin "1") (pinfunction "1_1") (pintype "passive"))
      (node (ref "U18") (pin "1") (pinfunction "Z_1") (pintype "bidirectional"))
    )
    (net (code "69") (name "Net-(U19-Z)") (class "Default")
      (node (ref "R119") (pin "1") (pinfunction "1_1") (pintype "passive"))
      (node (ref "U19") (pin "1") (pinfunction "Z_1") (pintype "bidirectional"))
    )
    (net (code "70") (name "Net-(U20A-1IN+)") (class "Default")
      (node (ref "R121") (pin "2") (pinfunction "2_2") (pintype "passive"))
      (node (ref "R122") (pin "1") (pinfunction "1_1") (pintype "passive"))
      (node (ref "U20") (pin "5") (pinfunction "1IN+_5") (pintype "input"))
    )
    (net (code "71") (name "Net-(U20A-1OUT)") (class "Default")
      (node (ref "R115") (pin "2") (pinfunction "2_2") (pintype "passive"))
      (node (ref "R118") (pin "1") (pinfunction "1_1") (pintype "passive"))
      (node (ref "R122") (pin "2") (pinfunction "2_2") (pintype "passive"))
      (node (ref "U20") (pin "2") (pinfunction "1OUT_2") (pintype "output"))
    )
    (net (code "72") (name "Net-(U20B-2IN+)") (class "Default")
      (node (ref "R133") (pin "2") (pinfunction "2_2") (pintype "passive"))
      (node (ref "R134") (pin "1") (pinfunction "1_1") (pintype "passive"))
      (node (ref "U20") (pin "7") (pinfunction "2IN+_7") (pintype "input"))
    )
    (net (code "73") (name "Net-(U20B-2OUT)") (class "Default")
      (node (ref "R125") (pin "2") (pinfunction "2_2") (pintype "passive"))
      (node (ref "R129") (pin "1") (pinfunction "1_1") (pintype "passive"))
      (node (ref "R134") (pin "2") (pinfunction "2_2") (pintype "passive"))
      (node (ref "U20") (pin "1") (pinfunction "2OUT_1") (pintype "output"))
    )
    (net (code "74") (name "Net-(U20C-3IN+)") (class "Default")
      (node (ref "R123") (pin "2") (pinfunction "2_2") (pintype "passive"))
      (node (ref "R124") (pin "1") (pinfunction "1_1") (pintype "passive"))
      (node (ref "U20") (pin "9") (pinfunction "3IN+_9") (pintype "input"))
    )
    (net (code "75") (name "Net-(U20C-3OUT)") (class "Default")
      (node (ref "R116") (pin "2") (pinfunction "2_2") (pintype "passive"))
      (node (ref "R120") (pin "1") (pinfunction "1_1") (pintype "passive"))
      (node (ref "R124") (pin "2") (pinfunction "2_2") (pintype "passive"))
      (node (ref "U20") (pin "14") (pinfunction "3OUT_14") (pintype "output"))
    )
    (net (code "76") (name "Net-(U20D-4IN+)") (class "Default")
      (node (ref "R131") (pin "2") (pinfunction "2_2") (pintype "passive"))
      (node (ref "R132") (pin "1") (pinfunction "1_1") (pintype "passive"))
      (node (ref "U20") (pin "11") (pinfunction "4IN+_11") (pintype "input"))
    )
    (net (code "77") (name "Net-(U20D-4OUT)") (class "Default")
      (node (ref "R126") (pin "2") (pinfunction "2_2") (pintype "passive"))
      (node (ref "R130") (pin "1") (pinfunction "1_1") (pintype "passive"))
      (node (ref "R132") (pin "2") (pinfunction "2_2") (pintype "passive"))
      (node (ref "U20") (pin "13") (pinfunction "4OUT_13") (pintype "output"))
    )
    (net (code "78") (name "Net-(U21-Z)") (class "Default")
      (node (ref "R127") (pin "1") (pinfunction "1_1") (pintype "passive"))
      (node (ref "U21") (pin "1") (pinfunction "Z_1") (pintype "bidirectional"))
    )
    (net (code "79") (name "Net-(U22-Z)") (class "Default")
      (node (ref "R128") (pin "1") (pinfunction "1_1") (pintype "passive"))
      (node (ref "U22") (pin "1") (pinfunction "Z_1") (pintype "bidirectional"))
    )
    (net (code "80") (name "Net-(U23A-+IN_A)") (class "Default")
      (node (ref "R135") (pin "1") (pinfunction "1_1") (pintype "passive"))
      (node (ref "R136") (pin "2") (pinfunction "2_2") (pintype "passive"))
      (node (ref "U23") (pin "3") (pinfunction "+IN_A_3") (pintype "input"))
    )
    (net (code "81") (name "unconnected-(U18-Y10-Pad21)") (class "Default")
      (node (ref "U18") (pin "21") (pinfunction "Y10_21") (pintype "bidirectional+no_connect"))
    )
    (net (code "82") (name "unconnected-(U18-Y11-Pad20)") (class "Default")
      (node (ref "U18") (pin "20") (pinfunction "Y11_20") (pintype "bidirectional+no_connect"))
    )
    (net (code "83") (name "unconnected-(U18-Y12-Pad19)") (class "Default")
      (node (ref "U18") (pin "19") (pinfunction "Y12_19") (pintype "bidirectional+no_connect"))
    )
    (net (code "84") (name "unconnected-(U18-Y13-Pad18)") (class "Default")
      (node (ref "U18") (pin "18") (pinfunction "Y13_18") (pintype "bidirectional+no_connect"))
    )
    (net (code "85") (name "unconnected-(U19-Y10-Pad21)") (class "Default")
      (node (ref "U19") (pin "21") (pinfunction "Y10_21") (pintype "bidirectional+no_connect"))
    )
    (net (code "86") (name "unconnected-(U19-Y11-Pad20)") (class "Default")
      (node (ref "U19") (pin "20") (pinfunction "Y11_20") (pintype "bidirectional+no_connect"))
    )
    (net (code "87") (name "unconnected-(U19-Y12-Pad19)") (class "Default")
      (node (ref "U19") (pin "19") (pinfunction "Y12_19") (pintype "bidirectional+no_connect"))
    )
    (net (code "88") (name "unconnected-(U19-Y13-Pad18)") (class "Default")
      (node (ref "U19") (pin "18") (pinfunction "Y13_18") (pintype "bidirectional+no_connect"))
    )
    (net (code "89") (name "unconnected-(U21-Y10-Pad21)") (class "Default")
      (node (ref "U21") (pin "21") (pinfunction "Y10_21") (pintype "bidirectional+no_connect"))
    )
    (net (code "90") (name "unconnected-(U21-Y11-Pad20)") (class "Default")
      (node (ref "U21") (pin "20") (pinfunction "Y11_20") (pintype "bidirectional+no_connect"))
    )
    (net (code "91") (name "unconnected-(U21-Y12-Pad19)") (class "Default")
      (node (ref "U21") (pin "19") (pinfunction "Y12_19") (pintype "bidirectional+no_connect"))
    )
    (net (code "92") (name "unconnected-(U21-Y13-Pad18)") (class "Default")
      (node (ref "U21") (pin "18") (pinfunction "Y13_18") (pintype "bidirectional+no_connect"))
    )
    (net (code "93") (name "unconnected-(U22-Y10-Pad21)") (class "Default")
      (node (ref "U22") (pin "21") (pinfunction "Y10_21") (pintype "bidirectional+no_connect"))
    )
    (net (code "94") (name "unconnected-(U22-Y11-Pad20)") (class "Default")
      (node (ref "U22") (pin "20") (pinfunction "Y11_20") (pintype "bidirectional+no_connect"))
    )
    (net (code "95") (name "unconnected-(U22-Y12-Pad19)") (class "Default")
      (node (ref "U22") (pin "19") (pinfunction "Y12_19") (pintype "bidirectional+no_connect"))
    )
    (net (code "96") (name "unconnected-(U22-Y13-Pad18)") (class "Default")
      (node (ref "U22") (pin "18") (pinfunction "Y13_18") (pintype "bidirectional+no_connect"))
    )
    (net (code "97") (name "unconnected-(U23B-+IN_B-Pad5)") (class "Default")
      (node (ref "U23") (pin "5") (pinfunction "+IN_B_5") (pintype "input+no_connect"))
    )
    (net (code "98") (name "unconnected-(U23B--IN_B-Pad6)") (class "Default")
      (node (ref "U23") (pin "6") (pinfunction "-IN_B_6") (pintype "input+no_connect"))
    )
    (net (code "99") (name "unconnected-(U23B-OUT_B-Pad7)") (class "Default")
      (node (ref "U23") (pin "7") (pinfunction "OUT_B_7") (pintype "output+no_connect"))
    )
  )
)
